# AG_TEX.net
KiCad netlist of a schematic drawn in EAGLE
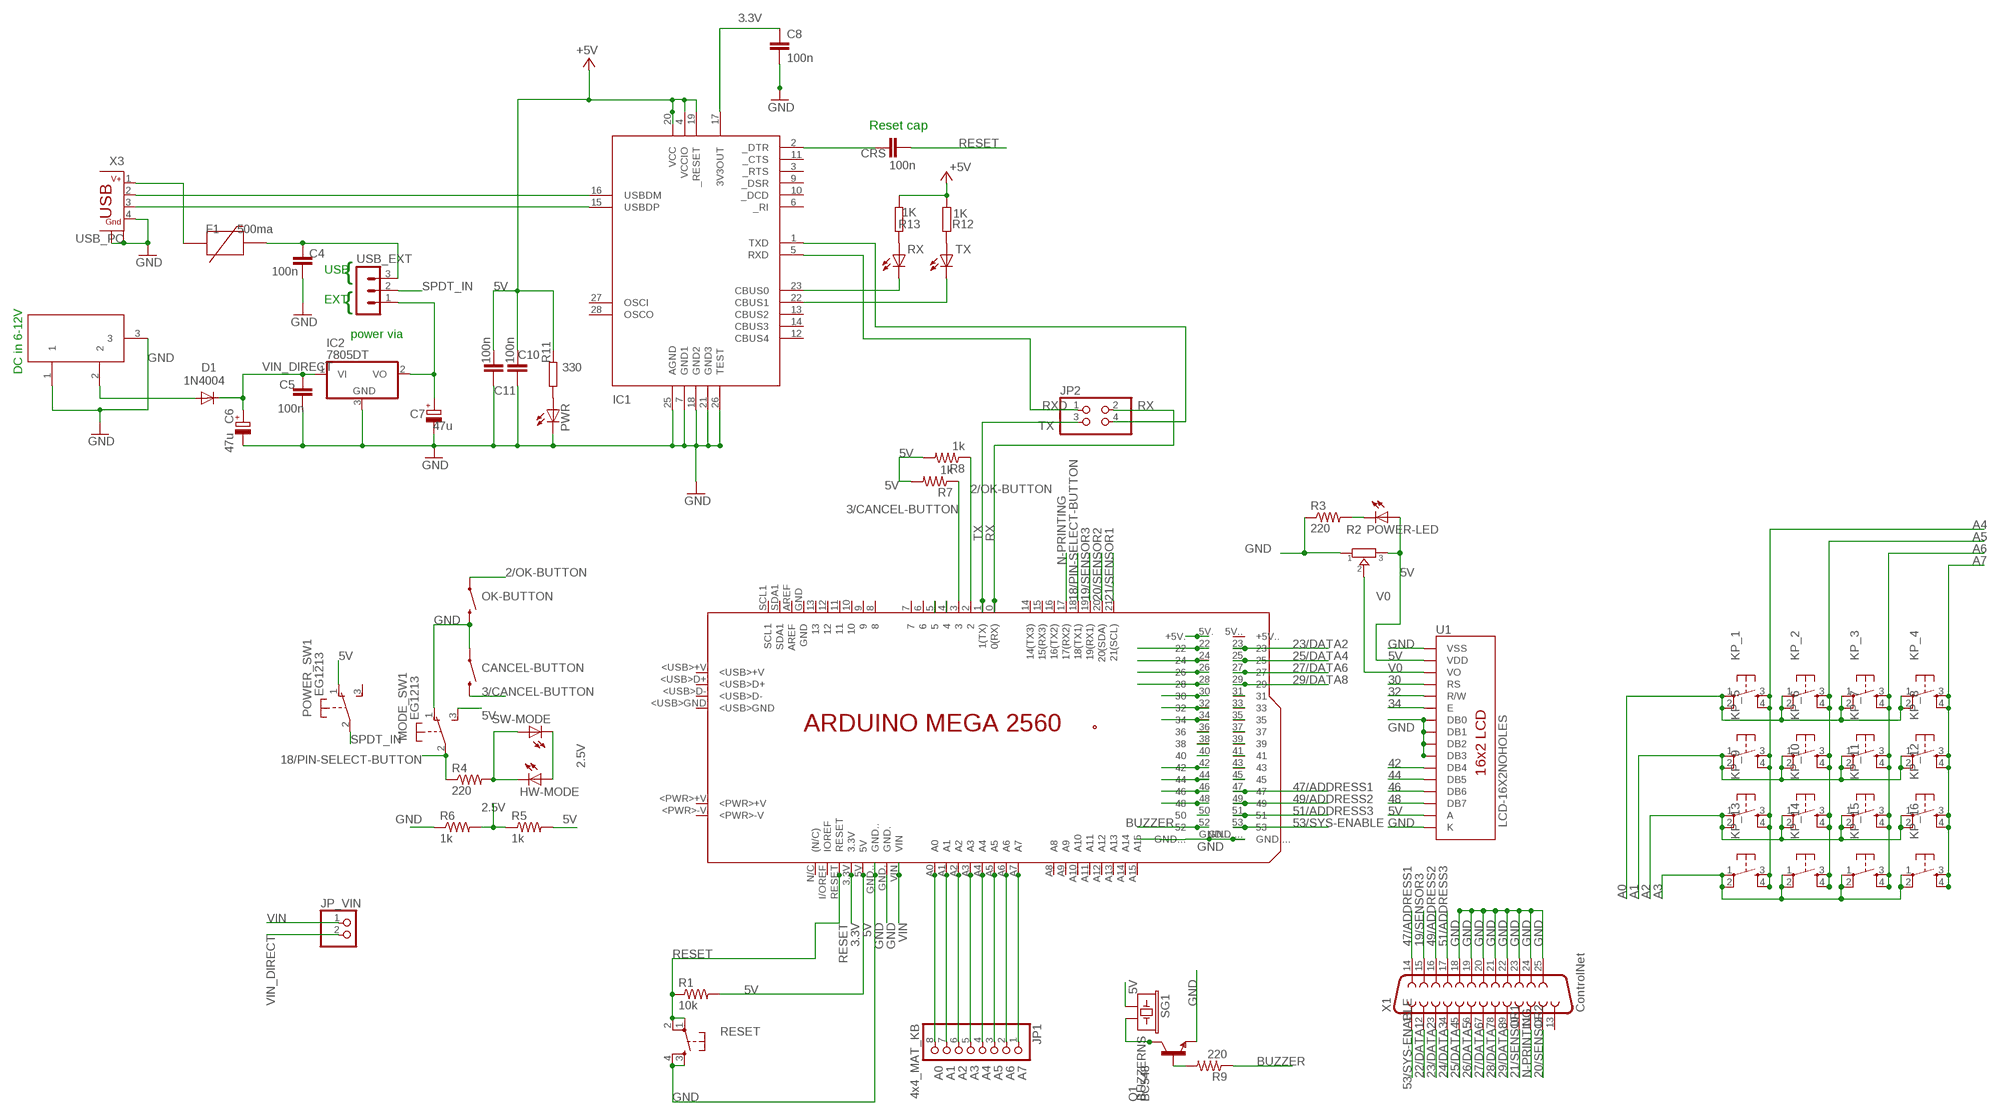
[diagram p0: schematic, sheet 1]

(export (version "E")
  (design (tool "Eeschema 10.0.6"))
  (components
    (comp (ref "C4")
      (value "100n")
      (footprint "eagle-import:C050-024X044")
      (libsource (lib "eagle-import") (part "C-EU050-024X044"))
    )
    (comp (ref "C5")
      (value "100n")
      (footprint "eagle-import:C050-024X044")
      (libsource (lib "eagle-import") (part "C-EU050-024X044"))
    )
    (comp (ref "C6")
      (value "47u")
      (footprint "eagle-import:E3,5-8")
      (libsource (lib "eagle-import") (part "CPOL-EUE3.5-8"))
    )
    (comp (ref "C7")
      (value "47u")
      (footprint "eagle-import:E3,5-8")
      (libsource (lib "eagle-import") (part "CPOL-EUE3.5-8"))
    )
    (comp (ref "C8")
      (value "100n")
      (footprint "eagle-import:C050-024X044")
      (libsource (lib "eagle-import") (part "C-EU050-024X044"))
    )
    (comp (ref "C10")
      (value "100n")
      (footprint "eagle-import:C050-024X044")
      (libsource (lib "eagle-import") (part "C-EU050-024X044"))
    )
    (comp (ref "C11")
      (value "100n")
      (footprint "eagle-import:C1206")
      (libsource (lib "eagle-import") (part "C-EUC1206"))
    )
    (comp (ref "CANCEL-BUTTON")
      (value "SWITCH-MOMENTARY-212MM")
      (footprint "eagle-import:TACTILE-PTH-12MM")
      (libsource (lib "eagle-import") (part "SWITCH-MOMENTARY-212MM"))
    )
    (comp (ref "CRS")
      (value "100n")
      (footprint "eagle-import:C050-024X044")
      (libsource (lib "eagle-import") (part "C-EU050-024X044"))
    )
    (comp (ref "D1")
      (value "1N4004")
      (footprint "eagle-import:DIODE-0.4")
      (libsource (lib "eagle-import") (part "DIODEPTH"))
    )
    (comp (ref "DC1")
      (value "9V in")
      (footprint "eagle-import:DC-21MM")
      (libsource (lib "eagle-import") (part "DC21MMX"))
    )
    (comp (ref "F1")
      (value "500ma")
      (footprint "eagle-import:PTC")
      (libsource (lib "eagle-import") (part "PTCPTH"))
    )
    (comp (ref "HW-MODE")
      (value "LED5MM")
      (footprint "eagle-import:LED5MM")
      (libsource (lib "eagle-import") (part "LED5MM"))
    )
    (comp (ref "IC1")
      (value "FT232RL")
      (footprint "eagle-import:SSOP28DB")
      (libsource (lib "eagle-import") (part "FT232RL-PINNED"))
    )
    (comp (ref "IC2")
      (value "7805DT")
      (footprint "eagle-import:TO252")
      (libsource (lib "eagle-import") (part "78DT05"))
    )
    (comp (ref "JP1")
      (value "4x4_MAT_KB")
      (footprint "eagle-import:1X08-CLEANBIG")
      (libsource (lib "eagle-import") (part "PINHD-1X8CLEANBIG"))
    )
    (comp (ref "JP2")
      (value "PINHD-2X2")
      (footprint "eagle-import:2X02")
      (libsource (lib "eagle-import") (part "PINHD-2X2"))
    )
    (comp (ref "JP_VIN")
      (value "PINHD-1X2")
      (footprint "eagle-import:1X02")
      (libsource (lib "eagle-import") (part "PINHD-1X2"))
    )
    (comp (ref "KP_1")
      (value "TAC_SWITCHPTH")
      (footprint "eagle-import:TACTILE-PTH")
      (libsource (lib "eagle-import") (part "TAC_SWITCHPTH"))
    )
    (comp (ref "KP_2")
      (value "TAC_SWITCHPTH")
      (footprint "eagle-import:TACTILE-PTH")
      (libsource (lib "eagle-import") (part "TAC_SWITCHPTH"))
    )
    (comp (ref "KP_3")
      (value "TAC_SWITCHPTH")
      (footprint "eagle-import:TACTILE-PTH")
      (libsource (lib "eagle-import") (part "TAC_SWITCHPTH"))
    )
    (comp (ref "KP_4")
      (value "TAC_SWITCHPTH")
      (footprint "eagle-import:TACTILE-PTH")
      (libsource (lib "eagle-import") (part "TAC_SWITCHPTH"))
    )
    (comp (ref "KP_5")
      (value "TAC_SWITCHPTH")
      (footprint "eagle-import:TACTILE-PTH")
      (libsource (lib "eagle-import") (part "TAC_SWITCHPTH"))
    )
    (comp (ref "KP_6")
      (value "TAC_SWITCHPTH")
      (footprint "eagle-import:TACTILE-PTH")
      (libsource (lib "eagle-import") (part "TAC_SWITCHPTH"))
    )
    (comp (ref "KP_7")
      (value "TAC_SWITCHPTH")
      (footprint "eagle-import:TACTILE-PTH")
      (libsource (lib "eagle-import") (part "TAC_SWITCHPTH"))
    )
    (comp (ref "KP_8")
      (value "TAC_SWITCHPTH")
      (footprint "eagle-import:TACTILE-PTH")
      (libsource (lib "eagle-import") (part "TAC_SWITCHPTH"))
    )
    (comp (ref "KP_9")
      (value "TAC_SWITCHPTH")
      (footprint "eagle-import:TACTILE-PTH")
      (libsource (lib "eagle-import") (part "TAC_SWITCHPTH"))
    )
    (comp (ref "KP_10")
      (value "TAC_SWITCHPTH")
      (footprint "eagle-import:TACTILE-PTH")
      (libsource (lib "eagle-import") (part "TAC_SWITCHPTH"))
    )
    (comp (ref "KP_11")
      (value "TAC_SWITCHPTH")
      (footprint "eagle-import:TACTILE-PTH")
      (libsource (lib "eagle-import") (part "TAC_SWITCHPTH"))
    )
    (comp (ref "KP_12")
      (value "TAC_SWITCHPTH")
      (footprint "eagle-import:TACTILE-PTH")
      (libsource (lib "eagle-import") (part "TAC_SWITCHPTH"))
    )
    (comp (ref "KP_13")
      (value "TAC_SWITCHPTH")
      (footprint "eagle-import:TACTILE-PTH")
      (libsource (lib "eagle-import") (part "TAC_SWITCHPTH"))
    )
    (comp (ref "KP_14")
      (value "TAC_SWITCHPTH")
      (footprint "eagle-import:TACTILE-PTH")
      (libsource (lib "eagle-import") (part "TAC_SWITCHPTH"))
    )
    (comp (ref "KP_15")
      (value "TAC_SWITCHPTH")
      (footprint "eagle-import:TACTILE-PTH")
      (libsource (lib "eagle-import") (part "TAC_SWITCHPTH"))
    )
    (comp (ref "KP_16")
      (value "TAC_SWITCHPTH")
      (footprint "eagle-import:TACTILE-PTH")
      (libsource (lib "eagle-import") (part "TAC_SWITCHPTH"))
    )
    (comp (ref "MODE_SW")
      (value "EG1213")
      (footprint "eagle-import:EG1213")
      (libsource (lib "eagle-import") (part "EG1213"))
    )
    (comp (ref "OK-BUTTON")
      (value "SWITCH-MOMENTARY-212MM")
      (footprint "eagle-import:TACTILE-PTH-12MM")
      (libsource (lib "eagle-import") (part "SWITCH-MOMENTARY-212MM"))
    )
    (comp (ref "PCB1")
      (value "ARDUINO_MEGA2560")
      (footprint "eagle-import:ARDUINO_MEGA2560")
      (libsource (lib "eagle-import") (part "ARDUINO_MEGA2560"))
    )
    (comp (ref "POWER-LED")
      (value "LED5MM")
      (footprint "eagle-import:LED5MM")
      (libsource (lib "eagle-import") (part "LED5MM"))
    )
    (comp (ref "POWER_SW")
      (value "EG1213")
      (footprint "eagle-import:EG1213")
      (libsource (lib "eagle-import") (part "EG1213"))
    )
    (comp (ref "PWR")
      (value "LED3MM")
      (footprint "eagle-import:LED3MM")
      (libsource (lib "eagle-import") (part "led_LED3MM"))
    )
    (comp (ref "Q1")
      (value "BC548")
      (footprint "eagle-import:TO92-EBC")
      (libsource (lib "eagle-import") (part "BC548"))
    )
    (comp (ref "R1")
      (value "10k")
      (footprint "eagle-import:0204_7")
      (libsource (lib "eagle-import") (part "R-US_0204/7"))
    )
    (comp (ref "R2")
      (value "TRIMMER-3306F")
      (footprint "eagle-import:TRIMMER_3306F")
      (libsource (lib "eagle-import") (part "TRIMMER-3306F"))
    )
    (comp (ref "R3")
      (value "220")
      (footprint "eagle-import:0204_7")
      (libsource (lib "eagle-import") (part "R-US_0204/7"))
    )
    (comp (ref "R4")
      (value "220")
      (footprint "eagle-import:0204_7")
      (libsource (lib "eagle-import") (part "R-US_0204/7"))
    )
    (comp (ref "R5")
      (value "1k")
      (footprint "eagle-import:0204_7")
      (libsource (lib "eagle-import") (part "R-US_0204/7"))
    )
    (comp (ref "R6")
      (value "1k")
      (footprint "eagle-import:0204_7")
      (libsource (lib "eagle-import") (part "R-US_0204/7"))
    )
    (comp (ref "R7")
      (value "1k")
      (footprint "eagle-import:0204_7")
      (libsource (lib "eagle-import") (part "R-US_0204/7"))
    )
    (comp (ref "R8")
      (value "1k")
      (footprint "eagle-import:0204_7")
      (libsource (lib "eagle-import") (part "R-US_0204/7"))
    )
    (comp (ref "R9")
      (value "220")
      (footprint "eagle-import:0204_7")
      (libsource (lib "eagle-import") (part "R-US_0204/7"))
    )
    (comp (ref "R11")
      (value "330")
      (footprint "eagle-import:0204_7")
      (libsource (lib "eagle-import") (part "R-EU_0204/7"))
    )
    (comp (ref "R12")
      (value "1K")
      (footprint "eagle-import:0204_7")
      (libsource (lib "eagle-import") (part "R-EU_0204/7"))
    )
    (comp (ref "R13")
      (value "1K")
      (footprint "eagle-import:0204_7")
      (libsource (lib "eagle-import") (part "R-EU_0204/7"))
    )
    (comp (ref "RESET")
      (value "TAC_SWITCHPTH")
      (footprint "eagle-import:TACTILE-PTH")
      (libsource (lib "eagle-import") (part "TAC_SWITCHPTH"))
    )
    (comp (ref "RX")
      (value "LED3MM")
      (footprint "eagle-import:LED3MM")
      (libsource (lib "eagle-import") (part "led_LED3MM"))
    )
    (comp (ref "SG1")
      (value "BUZZERNS")
      (footprint "eagle-import:BUZZER-12MM-NS")
      (libsource (lib "eagle-import") (part "BUZZERNS"))
    )
    (comp (ref "SW-MODE")
      (value "LED5MM")
      (footprint "eagle-import:LED5MM")
      (libsource (lib "eagle-import") (part "LED5MM"))
    )
    (comp (ref "TX")
      (value "LED3MM")
      (footprint "eagle-import:LED3MM")
      (libsource (lib "eagle-import") (part "led_LED3MM"))
    )
    (comp (ref "U1")
      (value "LCD-16X2NOHOLES")
      (footprint "eagle-import:LCD-16X2_NOHOLES")
      (libsource (lib "eagle-import") (part "LCD-16X2NOHOLES"))
    )
    (comp (ref "USB_EXT")
      (value "MA03-1")
      (footprint "eagle-import:MA03-1")
      (libsource (lib "eagle-import") (part "MA03-1"))
    )
    (comp (ref "X1")
      (value "ControlNet")
      (footprint "eagle-import:F25HP")
      (libsource (lib "eagle-import") (part "F25HP"))
    )
    (comp (ref "X3")
      (value "USB_PC")
      (footprint "eagle-import:USB-WSHIELDPADS")
      (libsource (lib "eagle-import") (part "CON-USB-B"))
    )
  )
  (nets
    (net (code "1") (name "+5V") (class "Default")
      (node (ref "C10") (pin "2") (pinfunction "2_2") (pintype "passive"))
      (node (ref "C11") (pin "2") (pinfunction "2_2") (pintype "passive"))
      (node (ref "IC1") (pin "19") (pinfunction "_RESET_19") (pintype "input"))
      (node (ref "IC1") (pin "20") (pinfunction "VCC_20") (pintype "power_in"))
      (node (ref "IC1") (pin "4") (pinfunction "VCCIO_4") (pintype "power_in"))
      (node (ref "MODE_SW") (pin "3") (pinfunction "S_3") (pintype "passive"))
      (node (ref "PCB1") (pin "5V") (pinfunction "5V_5V") (pintype "bidirectional"))
      (node (ref "PCB1") (pin "5V.") (pinfunction "+5V._5V.") (pintype "bidirectional"))
      (node (ref "POWER-LED") (pin "A") (pinfunction "A_A") (pintype "passive"))
      (node (ref "POWER_SW") (pin "1") (pinfunction "O_1") (pintype "passive"))
      (node (ref "R1") (pin "2") (pinfunction "2_2") (pintype "passive"))
      (node (ref "R11") (pin "1") (pinfunction "1_1") (pintype "passive"))
      (node (ref "R12") (pin "1") (pinfunction "1_1") (pintype "passive"))
      (node (ref "R13") (pin "1") (pinfunction "1_1") (pintype "passive"))
      (node (ref "R2") (pin "3") (pinfunction "3_3") (pintype "passive"))
      (node (ref "R5") (pin "2") (pinfunction "2_2") (pintype "passive"))
      (node (ref "R7") (pin "2") (pinfunction "2_2") (pintype "passive"))
      (node (ref "R8") (pin "2") (pinfunction "2_2") (pintype "passive"))
      (node (ref "SG1") (pin "+") (pinfunction "1_+") (pintype "passive"))
      (node (ref "U1") (pin "15") (pinfunction "A_15") (pintype "power_in"))
      (node (ref "U1") (pin "2") (pinfunction "VDD_2") (pintype "power_in"))
    )
    (net (code "2") (name "/2.5V") (class "Default")
      (node (ref "HW-MODE") (pin "A") (pinfunction "A_A") (pintype "passive"))
      (node (ref "R5") (pin "1") (pinfunction "1_1") (pintype "passive"))
      (node (ref "R6") (pin "2") (pinfunction "2_2") (pintype "passive"))
      (node (ref "SW-MODE") (pin "K") (pinfunction "C_K") (pintype "passive"))
    )
    (net (code "3") (name "/2{slash}OK-BUTTON") (class "Default")
      (node (ref "OK-BUTTON") (pin "1") (pinfunction "1_1") (pintype "passive"))
      (node (ref "PCB1") (pin "2") (pinfunction "2_2") (pintype "bidirectional"))
      (node (ref "R8") (pin "1") (pinfunction "1_1") (pintype "passive"))
    )
    (net (code "4") (name "/3.3V") (class "Default")
      (node (ref "C8") (pin "1") (pinfunction "1_1") (pintype "passive"))
      (node (ref "IC1") (pin "17") (pinfunction "3V3OUT_17") (pintype "output"))
      (node (ref "PCB1") (pin "3.3V") (pinfunction "3.3V_3.3V") (pintype "bidirectional"))
    )
    (net (code "5") (name "/3{slash}CANCEL-BUTTON") (class "Default")
      (node (ref "CANCEL-BUTTON") (pin "3") (pinfunction "2_3") (pintype "passive"))
      (node (ref "PCB1") (pin "3") (pinfunction "3_3") (pintype "bidirectional"))
      (node (ref "R7") (pin "1") (pinfunction "1_1") (pintype "passive"))
    )
    (net (code "6") (name "/18{slash}PIN-SELECT-BUTTON") (class "Default")
      (node (ref "MODE_SW") (pin "2") (pinfunction "P_2") (pintype "passive"))
      (node (ref "PCB1") (pin "18") (pinfunction "18(TX1)_18") (pintype "bidirectional"))
      (node (ref "R4") (pin "1") (pinfunction "1_1") (pintype "passive"))
    )
    (net (code "7") (name "/19{slash}SENSOR3") (class "Default")
      (node (ref "PCB1") (pin "19") (pinfunction "19(RX1)_19") (pintype "bidirectional"))
      (node (ref "X1") (pin "15") (pinfunction "15_15") (pintype "passive"))
    )
    (net (code "8") (name "/20{slash}SENSOR2") (class "Default")
      (node (ref "PCB1") (pin "20") (pinfunction "20(SDA)_20") (pintype "bidirectional"))
      (node (ref "X1") (pin "12") (pinfunction "12_12") (pintype "passive"))
    )
    (net (code "9") (name "/21{slash}SENSOR1") (class "Default")
      (node (ref "PCB1") (pin "21") (pinfunction "21(SCL)_21") (pintype "bidirectional"))
      (node (ref "X1") (pin "10") (pinfunction "10_10") (pintype "passive"))
    )
    (net (code "10") (name "/22{slash}DATA1") (class "Default")
      (node (ref "PCB1") (pin "22") (pinfunction "22_22") (pintype "bidirectional"))
      (node (ref "X1") (pin "2") (pinfunction "2_2") (pintype "passive"))
    )
    (net (code "11") (name "/23{slash}DATA2") (class "Default")
      (node (ref "PCB1") (pin "23") (pinfunction "23_23") (pintype "bidirectional"))
      (node (ref "X1") (pin "3") (pinfunction "3_3") (pintype "passive"))
    )
    (net (code "12") (name "/24{slash}DATA3") (class "Default")
      (node (ref "PCB1") (pin "24") (pinfunction "24_24") (pintype "bidirectional"))
      (node (ref "X1") (pin "4") (pinfunction "4_4") (pintype "passive"))
    )
    (net (code "13") (name "/25{slash}DATA4") (class "Default")
      (node (ref "PCB1") (pin "25") (pinfunction "25_25") (pintype "bidirectional"))
      (node (ref "X1") (pin "5") (pinfunction "5_5") (pintype "passive"))
    )
    (net (code "14") (name "/26{slash}DATA5") (class "Default")
      (node (ref "PCB1") (pin "26") (pinfunction "26_26") (pintype "bidirectional"))
      (node (ref "X1") (pin "6") (pinfunction "6_6") (pintype "passive"))
    )
    (net (code "15") (name "/27{slash}DATA6") (class "Default")
      (node (ref "PCB1") (pin "27") (pinfunction "27_27") (pintype "bidirectional"))
      (node (ref "X1") (pin "7") (pinfunction "7_7") (pintype "passive"))
    )
    (net (code "16") (name "/28{slash}DATA7") (class "Default")
      (node (ref "PCB1") (pin "28") (pinfunction "28_28") (pintype "bidirectional"))
      (node (ref "X1") (pin "8") (pinfunction "8_8") (pintype "passive"))
    )
    (net (code "17") (name "/29{slash}DATA8") (class "Default")
      (node (ref "PCB1") (pin "29") (pinfunction "29_29") (pintype "bidirectional"))
      (node (ref "X1") (pin "9") (pinfunction "9_9") (pintype "passive"))
    )
    (net (code "18") (name "/30") (class "Default")
      (node (ref "PCB1") (pin "30") (pinfunction "30_30") (pintype "bidirectional"))
      (node (ref "U1") (pin "4") (pinfunction "RS_4") (pintype "input"))
    )
    (net (code "19") (name "/32") (class "Default")
      (node (ref "PCB1") (pin "32") (pinfunction "32_32") (pintype "bidirectional"))
      (node (ref "U1") (pin "5") (pinfunction "R/W_5") (pintype "input"))
    )
    (net (code "20") (name "/34") (class "Default")
      (node (ref "PCB1") (pin "34") (pinfunction "34_34") (pintype "bidirectional"))
      (node (ref "U1") (pin "6") (pinfunction "E_6") (pintype "input"))
    )
    (net (code "21") (name "/42") (class "Default")
      (node (ref "PCB1") (pin "42") (pinfunction "42_42") (pintype "bidirectional"))
      (node (ref "U1") (pin "11") (pinfunction "DB4_11") (pintype "bidirectional"))
    )
    (net (code "22") (name "/44") (class "Default")
      (node (ref "PCB1") (pin "44") (pinfunction "44_44") (pintype "bidirectional"))
      (node (ref "U1") (pin "12") (pinfunction "DB5_12") (pintype "bidirectional"))
    )
    (net (code "23") (name "/46") (class "Default")
      (node (ref "PCB1") (pin "46") (pinfunction "46_46") (pintype "bidirectional"))
      (node (ref "U1") (pin "13") (pinfunction "DB6_13") (pintype "bidirectional"))
    )
    (net (code "24") (name "/47{slash}ADDRESS1") (class "Default")
      (node (ref "PCB1") (pin "47") (pinfunction "47_47") (pintype "bidirectional"))
      (node (ref "X1") (pin "14") (pinfunction "14_14") (pintype "passive"))
    )
    (net (code "25") (name "/48") (class "Default")
      (node (ref "PCB1") (pin "48") (pinfunction "48_48") (pintype "bidirectional"))
      (node (ref "U1") (pin "14") (pinfunction "DB7_14") (pintype "bidirectional"))
    )
    (net (code "26") (name "/49{slash}ADDRESS2") (class "Default")
      (node (ref "PCB1") (pin "49") (pinfunction "49_49") (pintype "bidirectional"))
      (node (ref "X1") (pin "16") (pinfunction "16_16") (pintype "passive"))
    )
    (net (code "27") (name "/51{slash}ADDRESS3") (class "Default")
      (node (ref "PCB1") (pin "51") (pinfunction "51_51") (pintype "bidirectional"))
      (node (ref "X1") (pin "17") (pinfunction "17_17") (pintype "passive"))
    )
    (net (code "28") (name "/53{slash}SYS-ENABLE") (class "Default")
      (node (ref "PCB1") (pin "53") (pinfunction "53_53") (pintype "bidirectional"))
      (node (ref "X1") (pin "1") (pinfunction "1_1") (pintype "passive"))
    )
    (net (code "29") (name "/A0") (class "Default")
      (node (ref "JP1") (pin "8") (pinfunction "8_8") (pintype "passive"))
      (node (ref "KP_1") (pin "1") (pinfunction "1_1") (pintype "passive"))
      (node (ref "KP_1") (pin "2") (pinfunction "2_2") (pintype "passive"))
      (node (ref "KP_2") (pin "1") (pinfunction "1_1") (pintype "passive"))
      (node (ref "KP_2") (pin "2") (pinfunction "2_2") (pintype "passive"))
      (node (ref "KP_3") (pin "1") (pinfunction "1_1") (pintype "passive"))
      (node (ref "KP_3") (pin "2") (pinfunction "2_2") (pintype "passive"))
      (node (ref "KP_4") (pin "1") (pinfunction "1_1") (pintype "passive"))
      (node (ref "KP_4") (pin "2") (pinfunction "2_2") (pintype "passive"))
      (node (ref "PCB1") (pin "A0") (pinfunction "A0_A0") (pintype "bidirectional"))
    )
    (net (code "30") (name "/A1") (class "Default")
      (node (ref "JP1") (pin "7") (pinfunction "7_7") (pintype "passive"))
      (node (ref "KP_5") (pin "1") (pinfunction "1_1") (pintype "passive"))
      (node (ref "KP_5") (pin "2") (pinfunction "2_2") (pintype "passive"))
      (node (ref "KP_6") (pin "1") (pinfunction "1_1") (pintype "passive"))
      (node (ref "KP_6") (pin "2") (pinfunction "2_2") (pintype "passive"))
      (node (ref "KP_7") (pin "1") (pinfunction "1_1") (pintype "passive"))
      (node (ref "KP_7") (pin "2") (pinfunction "2_2") (pintype "passive"))
      (node (ref "KP_8") (pin "1") (pinfunction "1_1") (pintype "passive"))
      (node (ref "KP_8") (pin "2") (pinfunction "2_2") (pintype "passive"))
      (node (ref "PCB1") (pin "A1") (pinfunction "A1_A1") (pintype "bidirectional"))
    )
    (net (code "31") (name "/A2") (class "Default")
      (node (ref "JP1") (pin "6") (pinfunction "6_6") (pintype "passive"))
      (node (ref "KP_10") (pin "1") (pinfunction "1_1") (pintype "passive"))
      (node (ref "KP_10") (pin "2") (pinfunction "2_2") (pintype "passive"))
      (node (ref "KP_11") (pin "1") (pinfunction "1_1") (pintype "passive"))
      (node (ref "KP_11") (pin "2") (pinfunction "2_2") (pintype "passive"))
      (node (ref "KP_12") (pin "1") (pinfunction "1_1") (pintype "passive"))
      (node (ref "KP_12") (pin "2") (pinfunction "2_2") (pintype "passive"))
      (node (ref "KP_9") (pin "1") (pinfunction "1_1") (pintype "passive"))
      (node (ref "KP_9") (pin "2") (pinfunction "2_2") (pintype "passive"))
      (node (ref "PCB1") (pin "A2") (pinfunction "A2_A2") (pintype "bidirectional"))
    )
    (net (code "32") (name "/A3") (class "Default")
      (node (ref "JP1") (pin "5") (pinfunction "5_5") (pintype "passive"))
      (node (ref "KP_13") (pin "1") (pinfunction "1_1") (pintype "passive"))
      (node (ref "KP_13") (pin "2") (pinfunction "2_2") (pintype "passive"))
      (node (ref "KP_14") (pin "1") (pinfunction "1_1") (pintype "passive"))
      (node (ref "KP_14") (pin "2") (pinfunction "2_2") (pintype "passive"))
      (node (ref "KP_15") (pin "1") (pinfunction "1_1") (pintype "passive"))
      (node (ref "KP_15") (pin "2") (pinfunction "2_2") (pintype "passive"))
      (node (ref "KP_16") (pin "1") (pinfunction "1_1") (pintype "passive"))
      (node (ref "KP_16") (pin "2") (pinfunction "2_2") (pintype "passive"))
      (node (ref "PCB1") (pin "A3") (pinfunction "A3_A3") (pintype "bidirectional"))
    )
    (net (code "33") (name "/A4") (class "Default")
      (node (ref "JP1") (pin "4") (pinfunction "4_4") (pintype "passive"))
      (node (ref "KP_1") (pin "3") (pinfunction "3_3") (pintype "passive"))
      (node (ref "KP_1") (pin "4") (pinfunction "4_4") (pintype "passive"))
      (node (ref "KP_13") (pin "3") (pinfunction "3_3") (pintype "passive"))
      (node (ref "KP_13") (pin "4") (pinfunction "4_4") (pintype "passive"))
      (node (ref "KP_5") (pin "3") (pinfunction "3_3") (pintype "passive"))
      (node (ref "KP_5") (pin "4") (pinfunction "4_4") (pintype "passive"))
      (node (ref "KP_9") (pin "3") (pinfunction "3_3") (pintype "passive"))
      (node (ref "KP_9") (pin "4") (pinfunction "4_4") (pintype "passive"))
      (node (ref "PCB1") (pin "A4") (pinfunction "A4_A4") (pintype "bidirectional"))
    )
    (net (code "34") (name "/A5") (class "Default")
      (node (ref "JP1") (pin "3") (pinfunction "3_3") (pintype "passive"))
      (node (ref "KP_10") (pin "3") (pinfunction "3_3") (pintype "passive"))
      (node (ref "KP_10") (pin "4") (pinfunction "4_4") (pintype "passive"))
      (node (ref "KP_14") (pin "3") (pinfunction "3_3") (pintype "passive"))
      (node (ref "KP_14") (pin "4") (pinfunction "4_4") (pintype "passive"))
      (node (ref "KP_2") (pin "3") (pinfunction "3_3") (pintype "passive"))
      (node (ref "KP_2") (pin "4") (pinfunction "4_4") (pintype "passive"))
      (node (ref "KP_6") (pin "3") (pinfunction "3_3") (pintype "passive"))
      (node (ref "KP_6") (pin "4") (pinfunction "4_4") (pintype "passive"))
      (node (ref "PCB1") (pin "A5") (pinfunction "A5_A5") (pintype "bidirectional"))
    )
    (net (code "35") (name "/A6") (class "Default")
      (node (ref "JP1") (pin "2") (pinfunction "2_2") (pintype "passive"))
      (node (ref "KP_11") (pin "3") (pinfunction "3_3") (pintype "passive"))
      (node (ref "KP_11") (pin "4") (pinfunction "4_4") (pintype "passive"))
      (node (ref "KP_15") (pin "3") (pinfunction "3_3") (pintype "passive"))
      (node (ref "KP_15") (pin "4") (pinfunction "4_4") (pintype "passive"))
      (node (ref "KP_3") (pin "3") (pinfunction "3_3") (pintype "passive"))
      (node (ref "KP_3") (pin "4") (pinfunction "4_4") (pintype "passive"))
      (node (ref "KP_7") (pin "3") (pinfunction "3_3") (pintype "passive"))
      (node (ref "KP_7") (pin "4") (pinfunction "4_4") (pintype "passive"))
      (node (ref "PCB1") (pin "A6") (pinfunction "A6_A6") (pintype "bidirectional"))
    )
    (net (code "36") (name "/A7") (class "Default")
      (node (ref "JP1") (pin "1") (pinfunction "1_1") (pintype "passive"))
      (node (ref "KP_12") (pin "3") (pinfunction "3_3") (pintype "passive"))
      (node (ref "KP_12") (pin "4") (pinfunction "4_4") (pintype "passive"))
      (node (ref "KP_16") (pin "3") (pinfunction "3_3") (pintype "passive"))
      (node (ref "KP_16") (pin "4") (pinfunction "4_4") (pintype "passive"))
      (node (ref "KP_4") (pin "3") (pinfunction "3_3") (pintype "passive"))
      (node (ref "KP_4") (pin "4") (pinfunction "4_4") (pintype "passive"))
      (node (ref "KP_8") (pin "3") (pinfunction "3_3") (pintype "passive"))
      (node (ref "KP_8") (pin "4") (pinfunction "4_4") (pintype "passive"))
      (node (ref "PCB1") (pin "A7") (pinfunction "A7_A7") (pintype "bidirectional"))
    )
    (net (code "37") (name "/BUZZER") (class "Default")
      (node (ref "PCB1") (pin "52") (pinfunction "52_52") (pintype "bidirectional"))
      (node (ref "R9") (pin "1") (pinfunction "1_1") (pintype "passive"))
    )
    (net (code "38") (name "/N-PRINTING") (class "Default")
      (node (ref "PCB1") (pin "17") (pinfunction "17(RX2)_17") (pintype "bidirectional"))
      (node (ref "X1") (pin "11") (pinfunction "11_11") (pintype "passive"))
    )
    (net (code "39") (name "/RESET") (class "Default")
      (node (ref "CRS") (pin "2") (pinfunction "2_2") (pintype "passive"))
      (node (ref "PCB1") (pin "RESET") (pinfunction "RESET_RESET") (pintype "bidirectional"))
      (node (ref "R1") (pin "1") (pinfunction "1_1") (pintype "passive"))
      (node (ref "RESET") (pin "1") (pinfunction "1_1") (pintype "passive"))
      (node (ref "RESET") (pin "2") (pinfunction "2_2") (pintype "passive"))
    )
    (net (code "40") (name "/RX") (class "Default")
      (node (ref "JP2") (pin "2") (pinfunction "2_2") (pintype "passive"))
      (node (ref "PCB1") (pin "0") (pinfunction "0(RX)_0") (pintype "bidirectional"))
    )
    (net (code "41") (name "/RXD") (class "Default")
      (node (ref "IC1") (pin "5") (pinfunction "RXD_5") (pintype "input"))
      (node (ref "JP2") (pin "1") (pinfunction "1_1") (pintype "passive"))
    )
    (net (code "42") (name "/SPDT_IN") (class "Default")
      (node (ref "POWER_SW") (pin "2") (pinfunction "P_2") (pintype "passive"))
      (node (ref "USB_EXT") (pin "2") (pinfunction "2_2") (pintype "passive"))
    )
    (net (code "43") (name "/TX") (class "Default")
      (node (ref "JP2") (pin "3") (pinfunction "3_3") (pintype "passive"))
      (node (ref "PCB1") (pin "1") (pinfunction "1(TX)_1") (pintype "bidirectional"))
    )
    (net (code "44") (name "/V0") (class "Default")
      (node (ref "R2") (pin "2") (pinfunction "2_2") (pintype "passive"))
      (node (ref "U1") (pin "3") (pinfunction "VO_3") (pintype "bidirectional"))
    )
    (net (code "45") (name "/VIN") (class "Default")
      (node (ref "JP_VIN") (pin "1") (pinfunction "1_1") (pintype "passive"))
      (node (ref "PCB1") (pin "VIN") (pinfunction "VIN_VIN") (pintype "bidirectional"))
    )
    (net (code "46") (name "/VIN_DIRECT") (class "Default")
      (node (ref "C5") (pin "2") (pinfunction "2_2") (pintype "passive"))
      (node (ref "C6") (pin "+") (pinfunction "+_+") (pintype "passive"))
      (node (ref "D1") (pin "C") (pinfunction "C_C") (pintype "passive"))
      (node (ref "IC2") (pin "1") (pinfunction "VI_1") (pintype "input"))
      (node (ref "JP_VIN") (pin "2") (pinfunction "2_2") (pintype "passive"))
    )
    (net (code "47") (name "GND") (class "Default")
      (node (ref "C10") (pin "1") (pinfunction "1_1") (pintype "passive"))
      (node (ref "C11") (pin "1") (pinfunction "1_1") (pintype "passive"))
      (node (ref "C4") (pin "1") (pinfunction "1_1") (pintype "passive"))
      (node (ref "C5") (pin "1") (pinfunction "1_1") (pintype "passive"))
      (node (ref "C6") (pin "-") (pinfunction "-_-") (pintype "passive"))
      (node (ref "C7") (pin "-") (pinfunction "-_-") (pintype "passive"))
      (node (ref "C8") (pin "2") (pinfunction "2_2") (pintype "passive"))
      (node (ref "CANCEL-BUTTON") (pin "1") (pinfunction "1_1") (pintype "passive"))
      (node (ref "DC1") (pin "1") (pinfunction "1_1") (pintype "power_in"))
      (node (ref "DC1") (pin "3") (pinfunction "3_3") (pintype "power_in"))
      (node (ref "IC1") (pin "18") (pinfunction "GND2_18") (pintype "power_in"))
      (node (ref "IC1") (pin "21") (pinfunction "GND3_21") (pintype "power_in"))
      (node (ref "IC1") (pin "25") (pinfunction "AGND_25") (pintype "power_in"))
      (node (ref "IC1") (pin "26") (pinfunction "TEST_26") (pintype "input"))
      (node (ref "IC1") (pin "7") (pinfunction "GND1_7") (pintype "power_in"))
      (node (ref "IC2") (pin "3") (pinfunction "GND_3") (pintype "passive"))
      (node (ref "MODE_SW") (pin "1") (pinfunction "O_1") (pintype "passive"))
      (node (ref "OK-BUTTON") (pin "3") (pinfunction "2_3") (pintype "passive"))
      (node (ref "PCB1") (pin "GND.") (pinfunction "GND._GND.") (pintype "bidirectional"))
      (node (ref "PCB1") (pin "GND..") (pinfunction "GND.._GND..") (pintype "bidirectional"))
      (node (ref "PCB1") (pin "GND...") (pinfunction "GND..._GND...") (pintype "bidirectional"))
      (node (ref "PCB1") (pin "GND....") (pinfunction "GND...._GND....") (pintype "bidirectional"))
      (node (ref "PWR") (pin "K") (pinfunction "C_K") (pintype "passive"))
      (node (ref "Q1") (pin "E") (pinfunction "E_E") (pintype "passive"))
      (node (ref "R2") (pin "1") (pinfunction "1_1") (pintype "passive"))
      (node (ref "R3") (pin "1") (pinfunction "1_1") (pintype "passive"))
      (node (ref "R6") (pin "1") (pinfunction "1_1") (pintype "passive"))
      (node (ref "RESET") (pin "3") (pinfunction "3_3") (pintype "passive"))
      (node (ref "RESET") (pin "4") (pinfunction "4_4") (pintype "passive"))
      (node (ref "U1") (pin "1") (pinfunction "VSS_1") (pintype "power_in"))
      (node (ref "U1") (pin "10") (pinfunction "DB3_10") (pintype "bidirectional"))
      (node (ref "U1") (pin "16") (pinfunction "K_16") (pintype "power_in"))
      (node (ref "U1") (pin "7") (pinfunction "DB0_7") (pintype "bidirectional"))
      (node (ref "U1") (pin "8") (pinfunction "DB1_8") (pintype "bidirectional"))
      (node (ref "U1") (pin "9") (pinfunction "DB2_9") (pintype "bidirectional"))
      (node (ref "X1") (pin "18") (pinfunction "18_18") (pintype "passive"))
      (node (ref "X1") (pin "19") (pinfunction "19_19") (pintype "passive"))
      (node (ref "X1") (pin "20") (pinfunction "20_20") (pintype "passive"))
      (node (ref "X1") (pin "21") (pinfunction "21_21") (pintype "passive"))
      (node (ref "X1") (pin "22") (pinfunction "22_22") (pintype "passive"))
      (node (ref "X1") (pin "23") (pinfunction "23_23") (pintype "passive"))
      (node (ref "X1") (pin "24") (pinfunction "24_24") (pintype "passive"))
      (node (ref "X1") (pin "25") (pinfunction "25_25") (pintype "passive"))
      (node (ref "X3") (pin "4") (pinfunction "4_4") (pintype "bidirectional"))
      (node (ref "X3") (pin "SH1") (pinfunction "GND_SH1") (pintype "power_in"))
      (node (ref "X3") (pin "SH2") (pinfunction "GND_SH2") (pintype "power_in"))
    )
    (net (code "48") (name "Net-(D1-PadA)") (class "Default")
      (node (ref "D1") (pin "A") (pinfunction "A_A") (pintype "passive"))
      (node (ref "DC1") (pin "2") (pinfunction "2_2") (pintype "power_in"))
    )
    (net (code "49") (name "Net-(F1-1)") (class "Default")
      (node (ref "F1") (pin "P$1") (pinfunction "1_P$1") (pintype "bidirectional"))
      (node (ref "X3") (pin "1") (pinfunction "1_1") (pintype "bidirectional"))
    )
    (net (code "50") (name "Net-(F1-2)") (class "Default")
      (node (ref "C4") (pin "2") (pinfunction "2_2") (pintype "passive"))
      (node (ref "F1") (pin "P$2") (pinfunction "2_P$2") (pintype "bidirectional"))
      (node (ref "USB_EXT") (pin "3") (pinfunction "3_3") (pintype "passive"))
    )
    (net (code "51") (name "Net-(HW-MODE-C)") (class "Default")
      (node (ref "HW-MODE") (pin "K") (pinfunction "C_K") (pintype "passive"))
      (node (ref "R4") (pin "2") (pinfunction "2_2") (pintype "passive"))
      (node (ref "SW-MODE") (pin "A") (pinfunction "A_A") (pintype "passive"))
    )
    (net (code "52") (name "Net-(IC1-CBUS0)") (class "Default")
      (node (ref "IC1") (pin "23") (pinfunction "CBUS0_23") (pintype "bidirectional"))
      (node (ref "RX") (pin "K") (pinfunction "C_K") (pintype "passive"))
    )
    (net (code "53") (name "Net-(IC1-CBUS1)") (class "Default")
      (node (ref "IC1") (pin "22") (pinfunction "CBUS1_22") (pintype "bidirectional"))
      (node (ref "TX") (pin "K") (pinfunction "C_K") (pintype "passive"))
    )
    (net (code "54") (name "Net-(IC1-TXD)") (class "Default")
      (node (ref "IC1") (pin "1") (pinfunction "TXD_1") (pintype "output"))
      (node (ref "JP2") (pin "4") (pinfunction "4_4") (pintype "passive"))
    )
    (net (code "55") (name "Net-(IC1-USBDM)") (class "Default")
      (node (ref "IC1") (pin "16") (pinfunction "USBDM_16") (pintype "bidirectional"))
      (node (ref "X3") (pin "2") (pinfunction "2_2") (pintype "bidirectional"))
    )
    (net (code "56") (name "Net-(IC1-USBDP)") (class "Default")
      (node (ref "IC1") (pin "15") (pinfunction "USBDP_15") (pintype "bidirectional"))
      (node (ref "X3") (pin "3") (pinfunction "3_3") (pintype "bidirectional"))
    )
    (net (code "57") (name "Net-(IC1-_DTR)") (class "Default")
      (node (ref "CRS") (pin "1") (pinfunction "1_1") (pintype "passive"))
      (node (ref "IC1") (pin "2") (pinfunction "_DTR_2") (pintype "output"))
    )
    (net (code "58") (name "Net-(IC2-VO)") (class "Default")
      (node (ref "C7") (pin "+") (pinfunction "+_+") (pintype "passive"))
      (node (ref "IC2") (pin "2") (pinfunction "VO_2") (pintype "passive"))
      (node (ref "USB_EXT") (pin "1") (pinfunction "1_1") (pintype "passive"))
    )
    (net (code "59") (name "Net-(POWER-LED-C)") (class "Default")
      (node (ref "POWER-LED") (pin "K") (pinfunction "C_K") (pintype "passive"))
      (node (ref "R3") (pin "2") (pinfunction "2_2") (pintype "passive"))
    )
    (net (code "60") (name "Net-(PWR-PadA)") (class "Default")
      (node (ref "PWR") (pin "A") (pinfunction "A_A") (pintype "passive"))
      (node (ref "R11") (pin "2") (pinfunction "2_2") (pintype "passive"))
    )
    (net (code "61") (name "Net-(Q1-PadB)") (class "Default")
      (node (ref "Q1") (pin "B") (pinfunction "B_B") (pintype "passive"))
      (node (ref "R9") (pin "2") (pinfunction "2_2") (pintype "passive"))
    )
    (net (code "62") (name "Net-(R12-Pad2)") (class "Default")
      (node (ref "R12") (pin "2") (pinfunction "2_2") (pintype "passive"))
      (node (ref "TX") (pin "A") (pinfunction "A_A") (pintype "passive"))
    )
    (net (code "63") (name "Net-(R13-Pad2)") (class "Default")
      (node (ref "R13") (pin "2") (pinfunction "2_2") (pintype "passive"))
      (node (ref "RX") (pin "A") (pinfunction "A_A") (pintype "passive"))
    )
    (net (code "64") (name "Net-(SG1-2)") (class "Default")
      (node (ref "Q1") (pin "C") (pinfunction "C_C") (pintype "passive"))
      (node (ref "SG1") (pin "-") (pinfunction "2_-") (pintype "passive"))
    )
    (net (code "65") (name "unconnected-(IC1-CBUS2-Pad13)") (class "Default")
      (node (ref "IC1") (pin "13") (pinfunction "CBUS2_13") (pintype "bidirectional"))
    )
    (net (code "66") (name "unconnected-(IC1-CBUS3-Pad14)") (class "Default")
      (node (ref "IC1") (pin "14") (pinfunction "CBUS3_14") (pintype "bidirectional"))
    )
    (net (code "67") (name "unconnected-(IC1-CBUS4-Pad12)") (class "Default")
      (node (ref "IC1") (pin "12") (pinfunction "CBUS4_12") (pintype "bidirectional"))
    )
    (net (code "68") (name "unconnected-(IC1-OSCI-Pad27)") (class "Default")
      (node (ref "IC1") (pin "27") (pinfunction "OSCI_27") (pintype "input"))
    )
    (net (code "69") (name "unconnected-(IC1-OSCO-Pad28)") (class "Default")
      (node (ref "IC1") (pin "28") (pinfunction "OSCO_28") (pintype "output"))
    )
    (net (code "70") (name "unconnected-(IC1-_CTS-Pad11)") (class "Default")
      (node (ref "IC1") (pin "11") (pinfunction "_CTS_11") (pintype "input"))
    )
    (net (code "71") (name "unconnected-(IC1-_DCD-Pad10)") (class "Default")
      (node (ref "IC1") (pin "10") (pinfunction "_DCD_10") (pintype "input"))
    )
    (net (code "72") (name "unconnected-(IC1-_DSR-Pad9)") (class "Default")
      (node (ref "IC1") (pin "9") (pinfunction "_DSR_9") (pintype "input"))
    )
    (net (code "73") (name "unconnected-(IC1-_RI-Pad6)") (class "Default")
      (node (ref "IC1") (pin "6") (pinfunction "_RI_6") (pintype "input"))
    )
    (net (code "74") (name "unconnected-(IC1-_RTS-Pad3)") (class "Default")
      (node (ref "IC1") (pin "3") (pinfunction "_RTS_3") (pintype "output"))
    )
    (net (code "75") (name "unconnected-(PCB1-(N{slash}C)-PadN{slash}C)") (class "Default")
      (node (ref "PCB1") (pin "N/C") (pinfunction "(N/C)_N/C") (pintype "bidirectional"))
    )
    (net (code "76") (name "unconnected-(PCB1-+5V..-Pad5V..)") (class "Default")
      (node (ref "PCB1") (pin "5V..") (pinfunction "+5V.._5V..") (pintype "bidirectional"))
    )
    (net (code "77") (name "unconnected-(PCB1-14(TX3)-Pad14)") (class "Default")
      (node (ref "PCB1") (pin "14") (pinfunction "14(TX3)_14") (pintype "bidirectional"))
    )
    (net (code "78") (name "unconnected-(PCB1-15(RX3)-Pad15)") (class "Default")
      (node (ref "PCB1") (pin "15") (pinfunction "15(RX3)_15") (pintype "bidirectional"))
    )
    (net (code "79") (name "unconnected-(PCB1-16(TX2)-Pad16)") (class "Default")
      (node (ref "PCB1") (pin "16") (pinfunction "16(TX2)_16") (pintype "bidirectional"))
    )
    (net (code "80") (name "unconnected-(PCB1-IOREF-PadI{slash}OREF)") (class "Default")
      (node (ref "PCB1") (pin "I/OREF") (pinfunction "IOREF_I/OREF") (pintype "bidirectional"))
    )
    (net (code "81") (name "unconnected-(PCB1-Pad4)") (class "Default")
      (node (ref "PCB1") (pin "4") (pinfunction "4_4") (pintype "bidirectional"))
    )
    (net (code "82") (name "unconnected-(PCB1-Pad5)") (class "Default")
      (node (ref "PCB1") (pin "5") (pinfunction "5_5") (pintype "bidirectional"))
    )
    (net (code "83") (name "unconnected-(PCB1-Pad6)") (class "Default")
      (node (ref "PCB1") (pin "6") (pinfunction "6_6") (pintype "bidirectional"))
    )
    (net (code "84") (name "unconnected-(PCB1-Pad7)") (class "Default")
      (node (ref "PCB1") (pin "7") (pinfunction "7_7") (pintype "bidirectional"))
    )
    (net (code "85") (name "unconnected-(PCB1-Pad8)") (class "Default")
      (node (ref "PCB1") (pin "8") (pinfunction "8_8") (pintype "bidirectional"))
    )
    (net (code "86") (name "unconnected-(PCB1-Pad9)") (class "Default")
      (node (ref "PCB1") (pin "9") (pinfunction "9_9") (pintype "bidirectional"))
    )
    (net (code "87") (name "unconnected-(PCB1-Pad10)") (class "Default")
      (node (ref "PCB1") (pin "10") (pinfunction "10_10") (pintype "bidirectional"))
    )
    (net (code "88") (name "unconnected-(PCB1-Pad11)") (class "Default")
      (node (ref "PCB1") (pin "11") (pinfunction "11_11") (pintype "bidirectional"))
    )
    (net (code "89") (name "unconnected-(PCB1-Pad12)") (class "Default")
      (node (ref "PCB1") (pin "12") (pinfunction "12_12") (pintype "bidirectional"))
    )
    (net (code "90") (name "unconnected-(PCB1-Pad13)") (class "Default")
      (node (ref "PCB1") (pin "13") (pinfunction "13_13") (pintype "bidirectional"))
    )
    (net (code "91") (name "unconnected-(PCB1-Pad31)") (class "Default")
      (node (ref "PCB1") (pin "31") (pinfunction "31_31") (pintype "bidirectional"))
    )
    (net (code "92") (name "unconnected-(PCB1-Pad33)") (class "Default")
      (node (ref "PCB1") (pin "33") (pinfunction "33_33") (pintype "bidirectional"))
    )
    (net (code "93") (name "unconnected-(PCB1-Pad35)") (class "Default")
      (node (ref "PCB1") (pin "35") (pinfunction "35_35") (pintype "bidirectional"))
    )
    (net (code "94") (name "unconnected-(PCB1-Pad36)") (class "Default")
      (node (ref "PCB1") (pin "36") (pinfunction "36_36") (pintype "bidirectional"))
    )
    (net (code "95") (name "unconnected-(PCB1-Pad37)") (class "Default")
      (node (ref "PCB1") (pin "37") (pinfunction "37_37") (pintype "bidirectional"))
    )
    (net (code "96") (name "unconnected-(PCB1-Pad38)") (class "Default")
      (node (ref "PCB1") (pin "38") (pinfunction "38_38") (pintype "bidirectional"))
    )
    (net (code "97") (name "unconnected-(PCB1-Pad39)") (class "Default")
      (node (ref "PCB1") (pin "39") (pinfunction "39_39") (pintype "bidirectional"))
    )
    (net (code "98") (name "unconnected-(PCB1-Pad40)") (class "Default")
      (node (ref "PCB1") (pin "40") (pinfunction "40_40") (pintype "bidirectional"))
    )
    (net (code "99") (name "unconnected-(PCB1-Pad41)") (class "Default")
      (node (ref "PCB1") (pin "41") (pinfunction "41_41") (pintype "bidirectional"))
    )
    (net (code "100") (name "unconnected-(PCB1-Pad43)") (class "Default")
      (node (ref "PCB1") (pin "43") (pinfunction "43_43") (pintype "bidirectional"))
    )
    (net (code "101") (name "unconnected-(PCB1-Pad45)") (class "Default")
      (node (ref "PCB1") (pin "45") (pinfunction "45_45") (pintype "bidirectional"))
    )
    (net (code "102") (name "unconnected-(PCB1-Pad50)") (class "Default")
      (node (ref "PCB1") (pin "50") (pinfunction "50_50") (pintype "bidirectional"))
    )
    (net (code "103") (name "unconnected-(PCB1-Pad<PWR>+V)") (class "Default")
      (node (ref "PCB1") (pin "<PWR>+V") (pinfunction "<PWR>+V_<PWR>+V") (pintype "no_connect"))
    )
    (net (code "104") (name "unconnected-(PCB1-Pad<PWR>-V)") (class "Default")
      (node (ref "PCB1") (pin "<PWR>-V") (pinfunction "<PWR>-V_<PWR>-V") (pintype "no_connect"))
    )
    (net (code "105") (name "unconnected-(PCB1-Pad<USB>+V)") (class "Default")
      (node (ref "PCB1") (pin "<USB>+V") (pinfunction "<USB>+V_<USB>+V") (pintype "no_connect"))
    )
    (net (code "106") (name "unconnected-(PCB1-Pad<USB>D+)") (class "Default")
      (node (ref "PCB1") (pin "<USB>D+") (pinfunction "<USB>D+_<USB>D+") (pintype "no_connect"))
    )
    (net (code "107") (name "unconnected-(PCB1-Pad<USB>D-)") (class "Default")
      (node (ref "PCB1") (pin "<USB>D-") (pinfunction "<USB>D-_<USB>D-") (pintype "no_connect"))
    )
    (net (code "108") (name "unconnected-(PCB1-Pad<USB>GND)") (class "Default")
      (node (ref "PCB1") (pin "<USB>GND") (pinfunction "<USB>GND_<USB>GND") (pintype "no_connect"))
    )
    (net (code "109") (name "unconnected-(PCB1-PadA8)") (class "Default")
      (node (ref "PCB1") (pin "A8") (pinfunction "A8_A8") (pintype "bidirectional"))
    )
    (net (code "110") (name "unconnected-(PCB1-PadA9)") (class "Default")
      (node (ref "PCB1") (pin "A9") (pinfunction "A9_A9") (pintype "bidirectional"))
    )
    (net (code "111") (name "unconnected-(PCB1-PadA10)") (class "Default")
      (node (ref "PCB1") (pin "A10") (pinfunction "A10_A10") (pintype "bidirectional"))
    )
    (net (code "112") (name "unconnected-(PCB1-PadA11)") (class "Default")
      (node (ref "PCB1") (pin "A11") (pinfunction "A11_A11") (pintype "bidirectional"))
    )
    (net (code "113") (name "unconnected-(PCB1-PadA12)") (class "Default")
      (node (ref "PCB1") (pin "A12") (pinfunction "A12_A12") (pintype "bidirectional"))
    )
    (net (code "114") (name "unconnected-(PCB1-PadA13)") (class "Default")
      (node (ref "PCB1") (pin "A13") (pinfunction "A13_A13") (pintype "bidirectional"))
    )
    (net (code "115") (name "unconnected-(PCB1-PadA14)") (class "Default")
      (node (ref "PCB1") (pin "A14") (pinfunction "A14_A14") (pintype "bidirectional"))
    )
    (net (code "116") (name "unconnected-(PCB1-PadA15)") (class "Default")
      (node (ref "PCB1") (pin "A15") (pinfunction "A15_A15") (pintype "bidirectional"))
    )
    (net (code "117") (name "unconnected-(PCB1-PadAREF)") (class "Default")
      (node (ref "PCB1") (pin "AREF") (pinfunction "AREF_AREF") (pintype "bidirectional"))
    )
    (net (code "118") (name "unconnected-(PCB1-PadGND)") (class "Default")
      (node (ref "PCB1") (pin "GND") (pinfunction "GND_GND") (pintype "bidirectional"))
    )
    (net (code "119") (name "unconnected-(PCB1-PadSCL1)") (class "Default")
      (node (ref "PCB1") (pin "SCL1") (pinfunction "SCL1_SCL1") (pintype "bidirectional"))
    )
    (net (code "120") (name "unconnected-(PCB1-PadSDA1)") (class "Default")
      (node (ref "PCB1") (pin "SDA1") (pinfunction "SDA1_SDA1") (pintype "bidirectional"))
    )
    (net (code "121") (name "unconnected-(POWER_SWA-S-Pad3)") (class "Default")
      (node (ref "POWER_SW") (pin "3") (pinfunction "S_3") (pintype "passive"))
    )
    (net (code "122") (name "unconnected-(X1-Pad13)") (class "Default")
      (node (ref "X1") (pin "13") (pinfunction "13_13") (pintype "passive"))
    )
  )
)
